# avr-hvsp-programmer.net
KiCad netlist of a schematic drawn in EAGLE
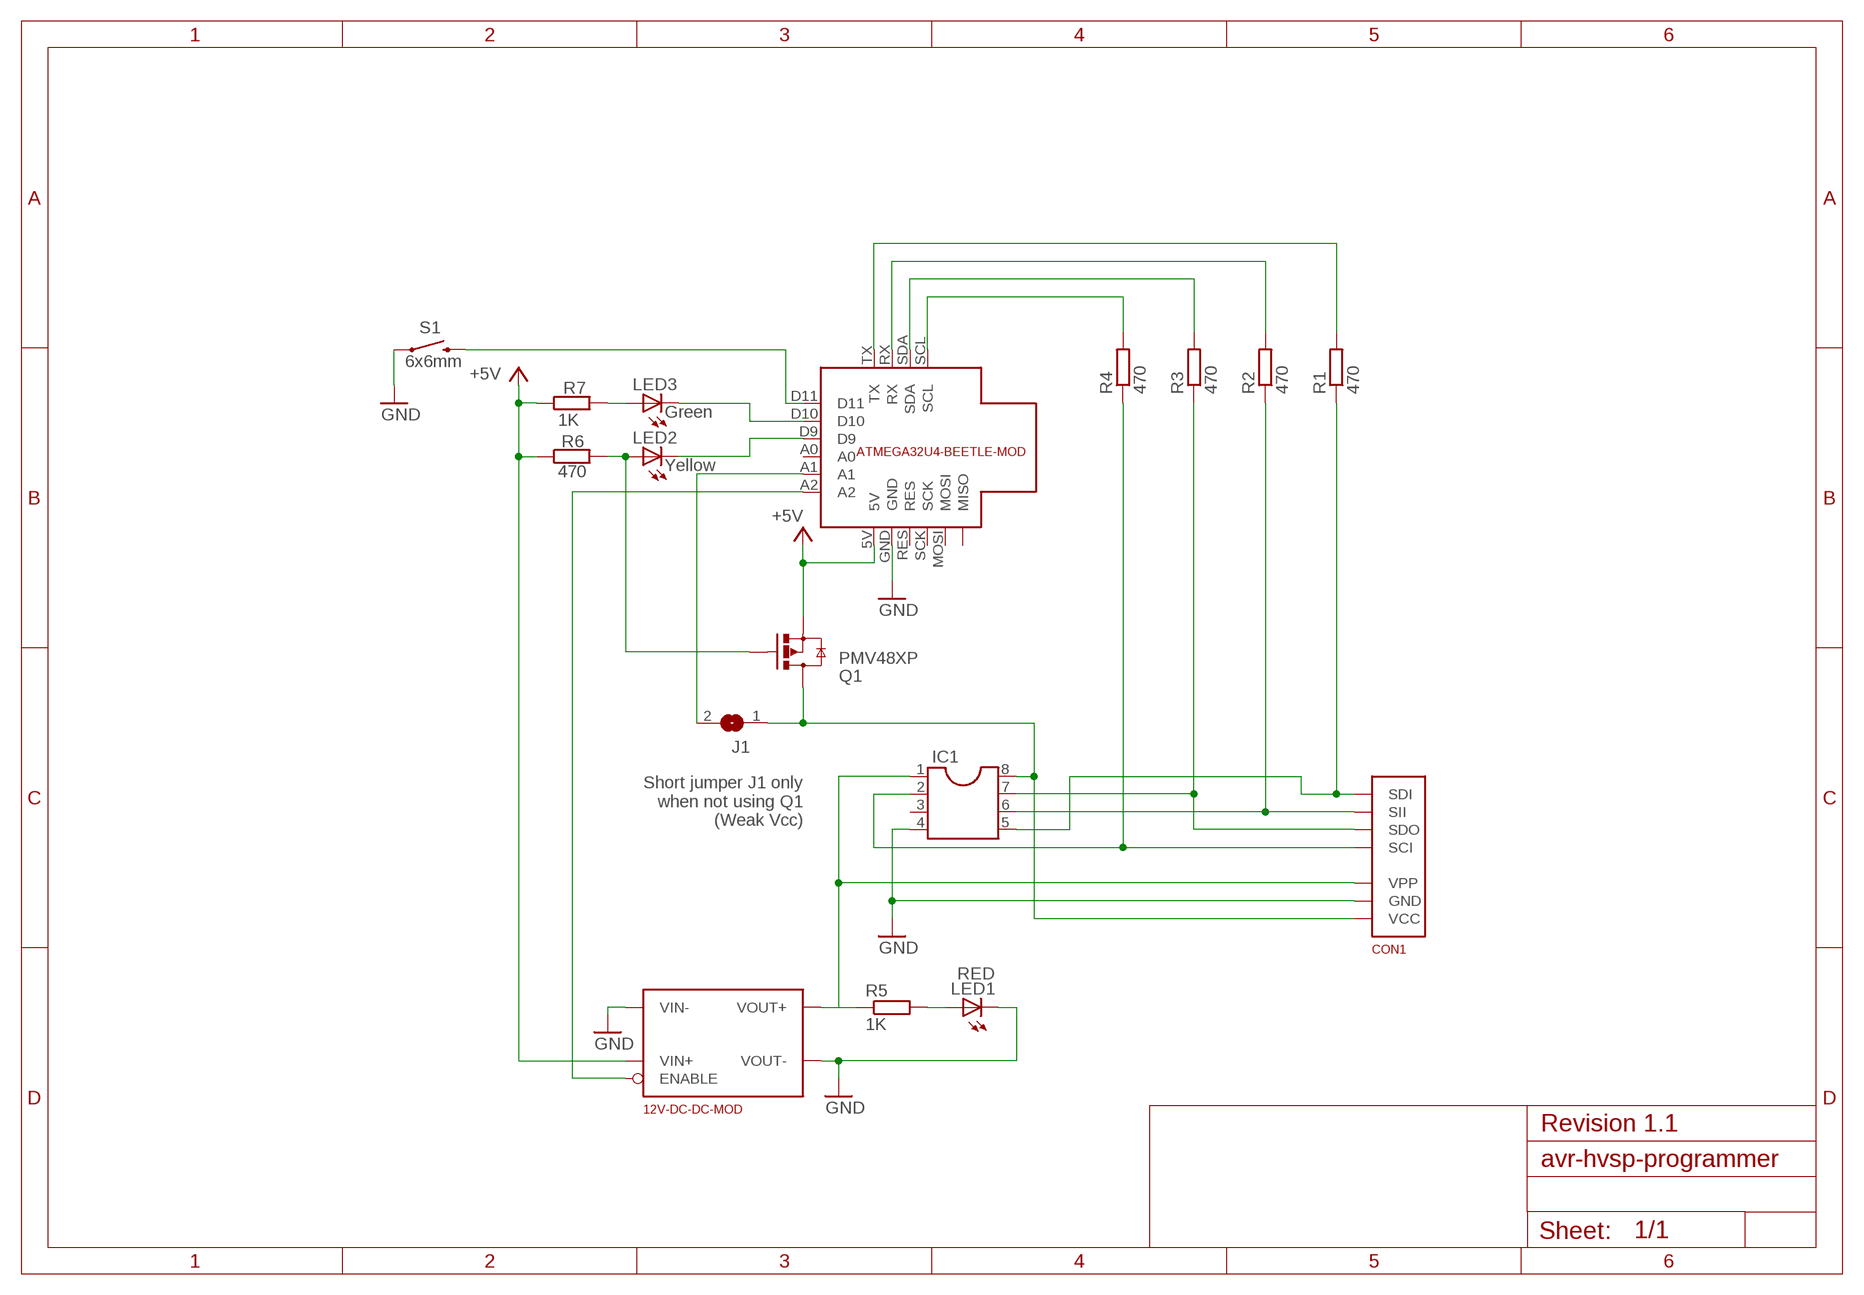
[diagram p0: schematic, sheet 1]

(export (version "E")
  (design (tool "Eeschema 10.0.6"))
  (components
    (comp (ref "12V-DC-DC-MOD")
      (value "12V-DC-DC-CONVERTER-WITH_ENABLE")
      (footprint "eagle-import:12V-DC-DC-CONVERTER-WITH-ENABLE")
      (libsource (lib "eagle-import") (part "12V-DC-DC-CONVERTER-WITH_ENABLE"))
    )
    (comp (ref "ATMEGA32U4-BEETLE-MOD")
      (value "ATMEGA32U4-BEETLE-BOARD")
      (footprint "eagle-import:ATMEGA32U4-BEETLE-BOARD")
      (libsource (lib "eagle-import") (part "ATMEGA32U4-BEETLE-BOARD"))
    )
    (comp (ref "CON1")
      (value "HVSP-HEADER")
      (footprint "eagle-import:HVSP-HEADER")
      (libsource (lib "eagle-import") (part "HVSP-HEADER"))
    )
    (comp (ref "IC1")
      (value "DIL8S")
      (footprint "eagle-import:SOCKET-08")
      (libsource (lib "eagle-import") (part "DIL8S"))
    )
    (comp (ref "J1") (value "SJ") (footprint "eagle-import:SJ") (libsource (lib "eagle-import") (part "SJ")))
    (comp (ref "LED1")
      (value "RED")
      (footprint "eagle-import:LED3MM")
      (libsource (lib "eagle-import") (part "LED3MM"))
    )
    (comp (ref "LED2")
      (value "Yellow")
      (footprint "eagle-import:LED3MM")
      (libsource (lib "eagle-import") (part "LED3MM"))
    )
    (comp (ref "LED3")
      (value "Green")
      (footprint "eagle-import:LED3MM")
      (libsource (lib "eagle-import") (part "LED3MM"))
    )
    (comp (ref "Q1")
      (value "PMV48XP")
      (footprint "eagle-import:SOT23-3")
      (fields (field (name "MANUFACTURER") "Nexperia") (field (name "MPN") "NX3008PBK,215"))
      (libsource (lib "eagle-import") (part "NX3008PBK"))
    )
    (comp (ref "R1")
      (value "470")
      (footprint "eagle-import:0207_7")
      (libsource (lib "eagle-import") (part "R-EU_0207/7"))
    )
    (comp (ref "R2")
      (value "470")
      (footprint "eagle-import:0207_7")
      (libsource (lib "eagle-import") (part "R-EU_0207/7"))
    )
    (comp (ref "R3")
      (value "470")
      (footprint "eagle-import:0207_7")
      (libsource (lib "eagle-import") (part "R-EU_0207/7"))
    )
    (comp (ref "R4")
      (value "470")
      (footprint "eagle-import:0207_7")
      (libsource (lib "eagle-import") (part "R-EU_0207/7"))
    )
    (comp (ref "R5")
      (value "1K")
      (footprint "eagle-import:0207_10")
      (libsource (lib "eagle-import") (part "R-EU_0207/10"))
    )
    (comp (ref "R6")
      (value "470")
      (footprint "eagle-import:0207_10")
      (libsource (lib "eagle-import") (part "R-EU_0207/10"))
    )
    (comp (ref "R7")
      (value "1K")
      (footprint "eagle-import:0207_10")
      (libsource (lib "eagle-import") (part "R-EU_0207/10"))
    )
    (comp (ref "S1")
      (value "6x6mm")
      (footprint "eagle-import:TACTILE_SWITCH_PTH_6.0MM")
      (libsource (lib "eagle-import") (part "MOMENTARY-SWITCH-SPST-PTH-6.0MM"))
    )
  )
  (nets
    (net (code "1") (name "+5V") (class "Default")
      (node (ref "12V-DC-DC-MOD") (pin "VIN+") (pinfunction "VIN+_VIN+") (pintype "power_in"))
      (node (ref "ATMEGA32U4-BEETLE-MOD") (pin "5V") (pinfunction "5V_5V") (pintype "bidirectional"))
      (node (ref "Q1") (pin "2") (pinfunction "S_2") (pintype "passive"))
      (node (ref "R6") (pin "1") (pinfunction "1_1") (pintype "passive"))
      (node (ref "R7") (pin "1") (pinfunction "1_1") (pintype "passive"))
    )
    (net (code "2") (name "GND") (class "Default")
      (node (ref "12V-DC-DC-MOD") (pin "VIN-") (pinfunction "VIN-_VIN-") (pintype "power_in"))
      (node (ref "12V-DC-DC-MOD") (pin "VOUT-") (pinfunction "VOUT-_VOUT-") (pintype "power_in"))
      (node (ref "ATMEGA32U4-BEETLE-MOD") (pin "GND") (pinfunction "GND_GND") (pintype "bidirectional"))
      (node (ref "CON1") (pin "GND") (pinfunction "GND_GND") (pintype "power_in"))
      (node (ref "IC1") (pin "4") (pinfunction "4_4") (pintype "passive"))
      (node (ref "LED1") (pin "K") (pinfunction "C_K") (pintype "passive"))
      (node (ref "S1") (pin "1") (pinfunction "1_1") (pintype "passive"))
    )
    (net (code "3") (name "Net-(12V-DC-DC-MOD-PadENABLE)") (class "Default")
      (node (ref "12V-DC-DC-MOD") (pin "ENABLE") (pinfunction "ENABLE_ENABLE") (pintype "input"))
      (node (ref "ATMEGA32U4-BEETLE-MOD") (pin "A2") (pinfunction "A2_A2") (pintype "bidirectional"))
    )
    (net (code "4") (name "Net-(12V-DC-DC-MOD-PadVOUT+)") (class "Default")
      (node (ref "12V-DC-DC-MOD") (pin "VOUT+") (pinfunction "VOUT+_VOUT+") (pintype "power_in"))
      (node (ref "CON1") (pin "VPP") (pinfunction "VPP_VPP") (pintype "power_in"))
      (node (ref "IC1") (pin "1") (pinfunction "1_1") (pintype "passive"))
      (node (ref "R5") (pin "1") (pinfunction "1_1") (pintype "passive"))
    )
    (net (code "5") (name "Net-(ATMEGA32U4-BEETLE-MOD-PadA1)") (class "Default")
      (node (ref "ATMEGA32U4-BEETLE-MOD") (pin "A1") (pinfunction "A1_A1") (pintype "bidirectional"))
      (node (ref "J1") (pin "2") (pinfunction "2_2") (pintype "passive"))
    )
    (net (code "6") (name "Net-(ATMEGA32U4-BEETLE-MOD-PadRX)") (class "Default")
      (node (ref "ATMEGA32U4-BEETLE-MOD") (pin "RX") (pinfunction "RX_RX") (pintype "bidirectional"))
      (node (ref "R2") (pin "2") (pinfunction "2_2") (pintype "passive"))
    )
    (net (code "7") (name "Net-(ATMEGA32U4-BEETLE-MOD-PadSCL)") (class "Default")
      (node (ref "ATMEGA32U4-BEETLE-MOD") (pin "SCL") (pinfunction "SCL_SCL") (pintype "bidirectional"))
      (node (ref "R4") (pin "2") (pinfunction "2_2") (pintype "passive"))
    )
    (net (code "8") (name "Net-(ATMEGA32U4-BEETLE-MOD-PadSDA)") (class "Default")
      (node (ref "ATMEGA32U4-BEETLE-MOD") (pin "SDA") (pinfunction "SDA_SDA") (pintype "bidirectional"))
      (node (ref "R3") (pin "2") (pinfunction "2_2") (pintype "passive"))
    )
    (net (code "9") (name "Net-(ATMEGA32U4-BEETLE-MOD-PadTX)") (class "Default")
      (node (ref "ATMEGA32U4-BEETLE-MOD") (pin "TX") (pinfunction "TX_TX") (pintype "bidirectional"))
      (node (ref "R1") (pin "2") (pinfunction "2_2") (pintype "passive"))
    )
    (net (code "10") (name "Net-(CON1-PadSCI)") (class "Default")
      (node (ref "CON1") (pin "SCI") (pinfunction "SCI_SCI") (pintype "power_in"))
      (node (ref "IC1") (pin "2") (pinfunction "2_2") (pintype "passive"))
      (node (ref "R4") (pin "1") (pinfunction "1_1") (pintype "passive"))
    )
    (net (code "11") (name "Net-(CON1-PadSDI)") (class "Default")
      (node (ref "CON1") (pin "SDI") (pinfunction "SDI_SDI") (pintype "power_in"))
      (node (ref "IC1") (pin "5") (pinfunction "5_5") (pintype "passive"))
      (node (ref "R1") (pin "1") (pinfunction "1_1") (pintype "passive"))
    )
    (net (code "12") (name "Net-(CON1-PadSDO)") (class "Default")
      (node (ref "CON1") (pin "SDO") (pinfunction "SDO_SDO") (pintype "power_in"))
      (node (ref "IC1") (pin "7") (pinfunction "7_7") (pintype "passive"))
      (node (ref "R3") (pin "1") (pinfunction "1_1") (pintype "passive"))
    )
    (net (code "13") (name "Net-(CON1-PadSII)") (class "Default")
      (node (ref "CON1") (pin "SII") (pinfunction "SII_SII") (pintype "power_in"))
      (node (ref "IC1") (pin "6") (pinfunction "6_6") (pintype "passive"))
      (node (ref "R2") (pin "1") (pinfunction "1_1") (pintype "passive"))
    )
    (net (code "14") (name "Net-(LED1-PadA)") (class "Default")
      (node (ref "LED1") (pin "A") (pinfunction "A_A") (pintype "passive"))
      (node (ref "R5") (pin "2") (pinfunction "2_2") (pintype "passive"))
    )
    (net (code "15") (name "Net-(LED2-C)") (class "Default")
      (node (ref "ATMEGA32U4-BEETLE-MOD") (pin "D9") (pinfunction "D9_D9") (pintype "bidirectional"))
      (node (ref "LED2") (pin "K") (pinfunction "C_K") (pintype "passive"))
    )
    (net (code "16") (name "Net-(LED3-C)") (class "Default")
      (node (ref "ATMEGA32U4-BEETLE-MOD") (pin "D10") (pinfunction "D10_D10") (pintype "bidirectional"))
      (node (ref "LED3") (pin "K") (pinfunction "C_K") (pintype "passive"))
    )
    (net (code "17") (name "Net-(LED3-PadA)") (class "Default")
      (node (ref "LED3") (pin "A") (pinfunction "A_A") (pintype "passive"))
      (node (ref "R7") (pin "2") (pinfunction "2_2") (pintype "passive"))
    )
    (net (code "18") (name "Net-(Q1-D)") (class "Default")
      (node (ref "CON1") (pin "VCC") (pinfunction "VCC_VCC") (pintype "power_in"))
      (node (ref "IC1") (pin "8") (pinfunction "8_8") (pintype "passive"))
      (node (ref "J1") (pin "1") (pinfunction "1_1") (pintype "passive"))
      (node (ref "Q1") (pin "3") (pinfunction "D_3") (pintype "passive"))
    )
    (net (code "19") (name "Net-(Q1-G)") (class "Default")
      (node (ref "LED2") (pin "A") (pinfunction "A_A") (pintype "passive"))
      (node (ref "Q1") (pin "1") (pinfunction "G_1") (pintype "passive"))
      (node (ref "R6") (pin "2") (pinfunction "2_2") (pintype "passive"))
    )
    (net (code "20") (name "Net-(S1-2)") (class "Default")
      (node (ref "ATMEGA32U4-BEETLE-MOD") (pin "D11") (pinfunction "D11_D11") (pintype "bidirectional"))
      (node (ref "S1") (pin "3") (pinfunction "2_3") (pintype "passive"))
    )
    (net (code "21") (name "unconnected-(ATMEGA32U4-BEETLE-MOD-PadA0)") (class "Default")
      (node (ref "ATMEGA32U4-BEETLE-MOD") (pin "A0") (pinfunction "A0_A0") (pintype "bidirectional"))
    )
    (net (code "22") (name "unconnected-(ATMEGA32U4-BEETLE-MOD-PadMISO)") (class "Default")
      (node (ref "ATMEGA32U4-BEETLE-MOD") (pin "MISO") (pinfunction "MISO_MISO") (pintype "bidirectional"))
    )
    (net (code "23") (name "unconnected-(ATMEGA32U4-BEETLE-MOD-PadMOSI)") (class "Default")
      (node (ref "ATMEGA32U4-BEETLE-MOD") (pin "MOSI") (pinfunction "MOSI_MOSI") (pintype "bidirectional"))
    )
    (net (code "24") (name "unconnected-(ATMEGA32U4-BEETLE-MOD-PadRES)") (class "Default")
      (node (ref "ATMEGA32U4-BEETLE-MOD") (pin "RES") (pinfunction "RES_RES") (pintype "bidirectional"))
    )
    (net (code "25") (name "unconnected-(ATMEGA32U4-BEETLE-MOD-PadSCK)") (class "Default")
      (node (ref "ATMEGA32U4-BEETLE-MOD") (pin "SCK") (pinfunction "SCK_SCK") (pintype "bidirectional"))
    )
    (net (code "26") (name "unconnected-(IC1-Pad3)") (class "Default")
      (node (ref "IC1") (pin "3") (pinfunction "3_3") (pintype "passive"))
    )
  )
)
